# STM3205P_VoltageControl.net
KiCad netlist of a schematic drawn in Altium Designer
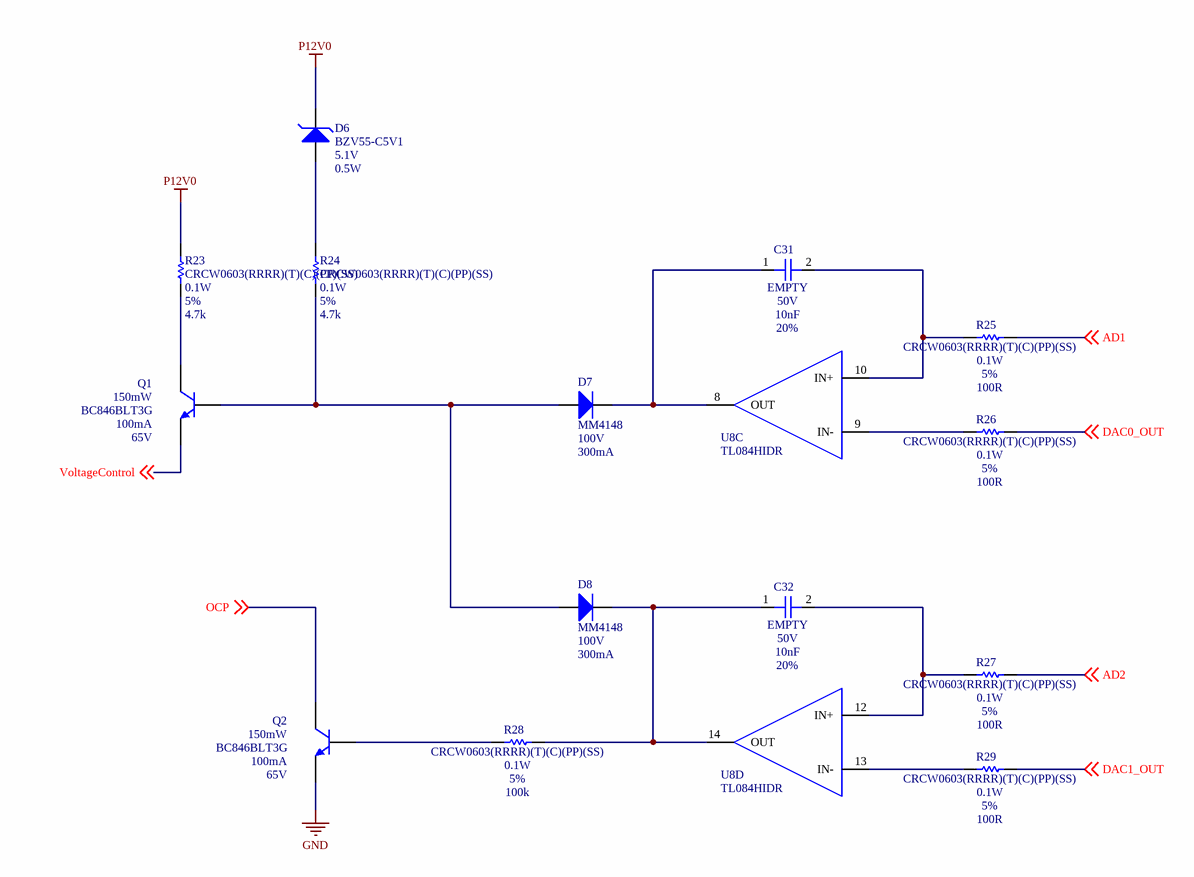
[diagram p0: STM3205P_VoltageControl.SchDoc]

(export (version "E")
  (design (tool "Eeschema 10.0.6"))
  (components
    (comp (ref "C31")
      (value "10nF")
      (footprint "CAP0603")
      (description "Surface Mount Multilayer Ceramic Chip Capacitors  for Commercial Applications")
      (fields
        (field (name "PARTNUMBER1") "EMPTY")
        (field (name "VOLTAGE") "50V")
        (field (name "TOLERANCE") "20%")
        (field (name "Comment") "CC0603")
        (field (name "PUBLISHER") "Lucas Moraes")
      )
      (libsource (lib "CeramicCapacitors") (part "CC0603"))
    )
    (comp (ref "C32")
      (value "10nF")
      (footprint "CAP0603")
      (description "Surface Mount Multilayer Ceramic Chip Capacitors  for Commercial Applications")
      (fields
        (field (name "PARTNUMBER1") "EMPTY")
        (field (name "VOLTAGE") "50V")
        (field (name "TOLERANCE") "20%")
        (field (name "Comment") "CC0603")
        (field (name "PUBLISHER") "Lucas Moraes")
      )
      (libsource (lib "CeramicCapacitors") (part "CC0603"))
    )
    (comp (ref "D6")
      (value "5.1V")
      (footprint "SOD-80C")
      (description "Zener Diodes 5.1V 0.5W")
      (fields
        (field (name "PARTNUMBER1") "BZV55-C5V1")
        (field (name "POWER") "0.5W")
        (field (name "Comment") "BZV55-C5V1")
        (field (name "PUBLISHER") "Lucas Moraes")
      )
      (libsource (lib "ZenerDiode") (part "BZV55-C5V1"))
    )
    (comp (ref "D7")
      (value "MM4148")
      (footprint "SOD-80C")
      (description "General Purpose Plastic Rectifier")
      (fields
        (field (name "PARTNUMBER1") "MM4148")
        (field (name "VRRM") "100V")
        (field (name "IF") "300mA")
        (field (name "PUBLISHER") "Lucas Moraes")
      )
      (libsource (lib "RectifierDiode") (part "MM4148"))
    )
    (comp (ref "D8")
      (value "MM4148")
      (footprint "SOD-80C")
      (description "General Purpose Plastic Rectifier")
      (fields
        (field (name "PARTNUMBER1") "MM4148")
        (field (name "VRRM") "100V")
        (field (name "IF") "300mA")
        (field (name "PUBLISHER") "Lucas Moraes")
      )
      (libsource (lib "RectifierDiode") (part "MM4148"))
    )
    (comp (ref "Q1")
      (value "BC846B")
      (footprint "SOT-23")
      (description "Transistor BJT NPN 65V 0.1A 150mW")
      (fields
        (field (name "POWER") "150mW")
        (field (name "PARTNUMBER1") "BC846BLT3G")
        (field (name "IC") "100mA")
        (field (name "VCE") "65V")
        (field (name "PUBLISHER") "Lucas Moraes")
      )
      (libsource (lib "BipolarJunctionTransistor") (part "BC846B"))
    )
    (comp (ref "Q2")
      (value "BC846B")
      (footprint "SOT-23")
      (description "Transistor BJT NPN 65V 0.1A 150mW")
      (fields
        (field (name "POWER") "150mW")
        (field (name "PARTNUMBER1") "BC846BLT3G")
        (field (name "IC") "100mA")
        (field (name "VCE") "65V")
        (field (name "PUBLISHER") "Lucas Moraes")
      )
      (libsource (lib "BipolarJunctionTransistor") (part "BC846B"))
    )
    (comp (ref "R23")
      (value "4.7k")
      (footprint "RES0603")
      (description "Thick Film Chip Resistors with CECC Approval,  available with Established Reliability")
      (fields
        (field (name "PARTNUMBER1") "CRCW0603(RRRR)(T)(C)(PP)(SS)")
        (field (name "POWER") "0.1W")
        (field (name "TOLERANCE") "5%")
        (field (name "Comment") "Chip Resistor")
        (field (name "PUBLISHER") "Lucas Moraes")
      )
      (libsource (lib "ResistorsFixed") (part "CRCW0603"))
    )
    (comp (ref "R24")
      (value "4.7k")
      (footprint "RES0603")
      (description "Thick Film Chip Resistors with CECC Approval,  available with Established Reliability")
      (fields
        (field (name "PARTNUMBER1") "CRCW0603(RRRR)(T)(C)(PP)(SS)")
        (field (name "POWER") "0.1W")
        (field (name "TOLERANCE") "5%")
        (field (name "Comment") "Chip Resistor")
        (field (name "PUBLISHER") "Lucas Moraes")
      )
      (libsource (lib "ResistorsFixed") (part "CRCW0603"))
    )
    (comp (ref "R25")
      (value "100R")
      (footprint "RES0603")
      (description "Thick Film Chip Resistors with CECC Approval,  available with Established Reliability")
      (fields
        (field (name "PARTNUMBER1") "CRCW0603(RRRR)(T)(C)(PP)(SS)")
        (field (name "POWER") "0.1W")
        (field (name "TOLERANCE") "5%")
        (field (name "Comment") "Chip Resistor")
        (field (name "PUBLISHER") "Lucas Moraes")
      )
      (libsource (lib "ResistorsFixed") (part "CRCW0603"))
    )
    (comp (ref "R26")
      (value "100R")
      (footprint "RES0603")
      (description "Thick Film Chip Resistors with CECC Approval,  available with Established Reliability")
      (fields
        (field (name "PARTNUMBER1") "CRCW0603(RRRR)(T)(C)(PP)(SS)")
        (field (name "POWER") "0.1W")
        (field (name "TOLERANCE") "5%")
        (field (name "Comment") "Chip Resistor")
        (field (name "PUBLISHER") "Lucas Moraes")
      )
      (libsource (lib "ResistorsFixed") (part "CRCW0603"))
    )
    (comp (ref "R27")
      (value "100R")
      (footprint "RES0603")
      (description "Thick Film Chip Resistors with CECC Approval,  available with Established Reliability")
      (fields
        (field (name "PARTNUMBER1") "CRCW0603(RRRR)(T)(C)(PP)(SS)")
        (field (name "POWER") "0.1W")
        (field (name "TOLERANCE") "5%")
        (field (name "Comment") "Chip Resistor")
        (field (name "PUBLISHER") "Lucas Moraes")
      )
      (libsource (lib "ResistorsFixed") (part "CRCW0603"))
    )
    (comp (ref "R28")
      (value "100k")
      (footprint "RES0603")
      (description "Thick Film Chip Resistors with CECC Approval,  available with Established Reliability")
      (fields
        (field (name "PARTNUMBER1") "CRCW0603(RRRR)(T)(C)(PP)(SS)")
        (field (name "POWER") "0.1W")
        (field (name "TOLERANCE") "5%")
        (field (name "Comment") "Chip Resistor")
        (field (name "PUBLISHER") "Lucas Moraes")
      )
      (libsource (lib "ResistorsFixed") (part "CRCW0603"))
    )
    (comp (ref "R29")
      (value "100R")
      (footprint "RES0603")
      (description "Thick Film Chip Resistors with CECC Approval,  available with Established Reliability")
      (fields
        (field (name "PARTNUMBER1") "CRCW0603(RRRR)(T)(C)(PP)(SS)")
        (field (name "POWER") "0.1W")
        (field (name "TOLERANCE") "5%")
        (field (name "Comment") "Chip Resistor")
        (field (name "PUBLISHER") "Lucas Moraes")
      )
      (libsource (lib "ResistorsFixed") (part "CRCW0603"))
    )
    (comp (ref "U8")
      (value "TL084HIDR")
      (footprint "SOIC-14-3.9mm")
      (description "Quad Operational Amplifiers RRIO")
      (fields (field (name "PARTNUMBER1") "TL084HIDR") (field (name "PUBLISHER") "Lucas Moraes"))
      (libsource (lib "Amplifiers") (part "TL084HIDR"))
    )
  )
  (nets
    (net (code "1") (name "AD1") (class "Default")
      (node (ref "R25") (pin "2") (pinfunction "2_2") (pintype "passive"))
    )
    (net (code "2") (name "AD2") (class "Default")
      (node (ref "R27") (pin "2") (pinfunction "2_2") (pintype "passive"))
    )
    (net (code "3") (name "DAC0_OUT") (class "Default")
      (node (ref "R26") (pin "2") (pinfunction "2_2") (pintype "passive"))
    )
    (net (code "4") (name "DAC1_OUT") (class "Default")
      (node (ref "R29") (pin "2") (pinfunction "2_2") (pintype "passive"))
    )
    (net (code "5") (name "GND") (class "Default")
      (node (ref "Q2") (pin "2") (pinfunction "E_2") (pintype "passive"))
    )
    (net (code "6") (name "Net-(D6-PadA)") (class "Default")
      (node (ref "D6") (pin "A") (pinfunction "A_A") (pintype "passive"))
      (node (ref "R24") (pin "2") (pinfunction "2_2") (pintype "passive"))
    )
    (net (code "7") (name "Net-(Q1-B)") (class "Default")
      (node (ref "D7") (pin "A") (pinfunction "A_A") (pintype "passive"))
      (node (ref "D8") (pin "A") (pinfunction "A_A") (pintype "passive"))
      (node (ref "Q1") (pin "1") (pinfunction "B_1") (pintype "passive"))
      (node (ref "R24") (pin "1") (pinfunction "1_1") (pintype "passive"))
    )
    (net (code "8") (name "Net-(Q1-C)") (class "Default")
      (node (ref "Q1") (pin "3") (pinfunction "C_3") (pintype "passive"))
      (node (ref "R23") (pin "1") (pinfunction "1_1") (pintype "passive"))
    )
    (net (code "9") (name "Net-(Q2-B)") (class "Default")
      (node (ref "Q2") (pin "1") (pinfunction "B_1") (pintype "passive"))
      (node (ref "R28") (pin "1") (pinfunction "1_1") (pintype "passive"))
    )
    (net (code "10") (name "Net-(U8C-IN+)") (class "Default")
      (node (ref "C31") (pin "2") (pinfunction "2_2") (pintype "passive"))
      (node (ref "R25") (pin "1") (pinfunction "1_1") (pintype "passive"))
      (node (ref "U8") (pin "10") (pinfunction "IN+_10") (pintype "passive"))
    )
    (net (code "11") (name "Net-(U8C-IN-)") (class "Default")
      (node (ref "R26") (pin "1") (pinfunction "1_1") (pintype "passive"))
      (node (ref "U8") (pin "9") (pinfunction "IN-_9") (pintype "passive"))
    )
    (net (code "12") (name "Net-(U8C-OUT)") (class "Default")
      (node (ref "C31") (pin "1") (pinfunction "1_1") (pintype "passive"))
      (node (ref "D7") (pin "K") (pinfunction "K_K") (pintype "passive"))
      (node (ref "U8") (pin "8") (pinfunction "OUT_8") (pintype "passive"))
    )
    (net (code "13") (name "Net-(U8D-IN+)") (class "Default")
      (node (ref "C32") (pin "2") (pinfunction "2_2") (pintype "passive"))
      (node (ref "R27") (pin "1") (pinfunction "1_1") (pintype "passive"))
      (node (ref "U8") (pin "12") (pinfunction "IN+_12") (pintype "passive"))
    )
    (net (code "14") (name "Net-(U8D-IN-)") (class "Default")
      (node (ref "R29") (pin "1") (pinfunction "1_1") (pintype "passive"))
      (node (ref "U8") (pin "13") (pinfunction "IN-_13") (pintype "passive"))
    )
    (net (code "15") (name "Net-(U8D-OUT)") (class "Default")
      (node (ref "C32") (pin "1") (pinfunction "1_1") (pintype "passive"))
      (node (ref "D8") (pin "K") (pinfunction "K_K") (pintype "passive"))
      (node (ref "R28") (pin "2") (pinfunction "2_2") (pintype "passive"))
      (node (ref "U8") (pin "14") (pinfunction "OUT_14") (pintype "passive"))
    )
    (net (code "16") (name "OCP") (class "Default")
      (node (ref "Q2") (pin "3") (pinfunction "C_3") (pintype "passive"))
    )
    (net (code "17") (name "P12V0") (class "Default")
      (node (ref "D6") (pin "K") (pinfunction "K_K") (pintype "passive"))
      (node (ref "R23") (pin "2") (pinfunction "2_2") (pintype "passive"))
    )
    (net (code "18") (name "VoltageControl") (class "Default")
      (node (ref "Q1") (pin "2") (pinfunction "E_2") (pintype "passive"))
    )
  )
)
